# 2015_Receive_LCD.net
KiCad netlist of a schematic drawn in EAGLE
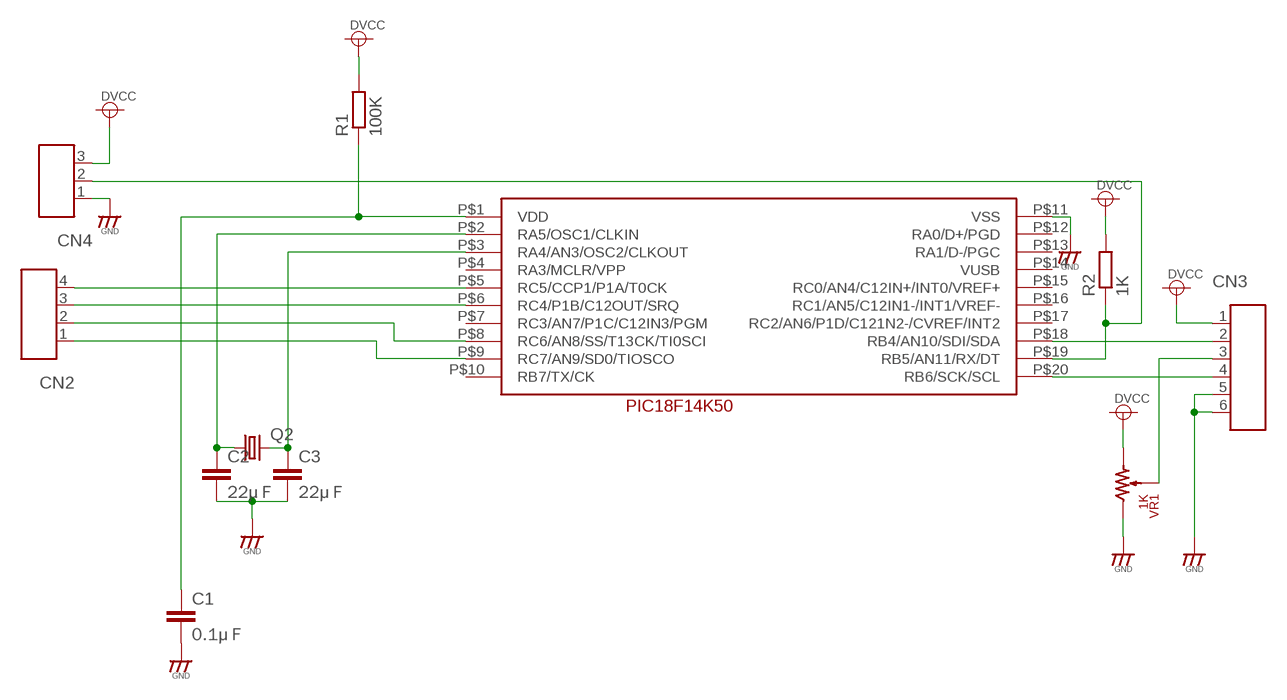
[diagram p0: schematic, sheet 1]

(export (version "E")
  (design (tool "Eeschema 10.0.6"))
  (components
    (comp (ref "C1")
      (value "0.1μＦ")
      (footprint "eagle-import:C025-025X050")
      (libsource (lib "eagle-import") (part "C-EU025-025X050"))
    )
    (comp (ref "C2")
      (value "22μＦ")
      (footprint "eagle-import:C025-025X050")
      (libsource (lib "eagle-import") (part "C-EU025-025X050"))
    )
    (comp (ref "C3")
      (value "22μＦ")
      (footprint "eagle-import:C025-025X050")
      (libsource (lib "eagle-import") (part "C-EU025-025X050"))
    )
    (comp (ref "CN2")
      (value "CON_4P")
      (footprint "eagle-import:CON_HRS_DIP_4")
      (libsource (lib "eagle-import") (part "CON_4P"))
    )
    (comp (ref "CN3")
      (value "CON_6P")
      (footprint "eagle-import:CON_HRS_DIP_6")
      (libsource (lib "eagle-import") (part "CON_6P"))
    )
    (comp (ref "CN4")
      (value "CON_3P")
      (footprint "eagle-import:CON_HRS_DIP_3")
      (libsource (lib "eagle-import") (part "CON_3P"))
    )
    (comp (ref "IC1")
      (value "PIC18F14K50")
      (footprint "eagle-import:PIC18F14K50")
      (libsource (lib "eagle-import") (part "PIC18F14K50"))
    )
    (comp (ref "Q2")
      (value "CRYTALHC49U70")
      (footprint "eagle-import:HC49U70")
      (libsource (lib "eagle-import") (part "CRYTALHC49U70"))
    )
    (comp (ref "R1")
      (value "100K")
      (footprint "eagle-import:0204_7")
      (libsource (lib "eagle-import") (part "R-EU_0204/7"))
    )
    (comp (ref "R2")
      (value "1K")
      (footprint "eagle-import:0204_7")
      (libsource (lib "eagle-import") (part "R-EU_0204/7"))
    )
    (comp (ref "VR1")
      (value "1K")
      (footprint "eagle-import:TRM")
      (libsource (lib "eagle-import") (part "TRM"))
    )
  )
  (nets
    (net (code "1") (name "/RA3{slash}MCLR{slash}VPP") (class "Default")
      (node (ref "IC1") (pin "P$4") (pinfunction "RA3/MCLR/VPP_P$4") (pintype "power_in"))
    )
    (net (code "2") (name "DVCC") (class "Default")
      (node (ref "CN3") (pin "1") (pinfunction "1_1") (pintype "passive"))
      (node (ref "CN4") (pin "3") (pinfunction "3_3") (pintype "passive"))
      (node (ref "R1") (pin "2") (pinfunction "2_2") (pintype "passive"))
      (node (ref "R2") (pin "2") (pinfunction "2_2") (pintype "passive"))
      (node (ref "VR1") (pin "P$1") (pinfunction "P$1_P$1") (pintype "passive"))
    )
    (net (code "3") (name "GND") (class "Default")
      (node (ref "C1") (pin "2") (pinfunction "2_2") (pintype "passive"))
      (node (ref "C2") (pin "2") (pinfunction "2_2") (pintype "passive"))
      (node (ref "C3") (pin "2") (pinfunction "2_2") (pintype "passive"))
      (node (ref "CN3") (pin "5") (pinfunction "5_5") (pintype "passive"))
      (node (ref "CN3") (pin "6") (pinfunction "6_6") (pintype "passive"))
      (node (ref "CN4") (pin "1") (pinfunction "1_1") (pintype "passive"))
      (node (ref "IC1") (pin "P$11") (pinfunction "VSS_P$11") (pintype "power_in"))
      (node (ref "VR1") (pin "P$3") (pinfunction "P$3_P$3") (pintype "passive"))
    )
    (net (code "4") (name "Net-(CN3-Pad3)") (class "Default")
      (node (ref "CN3") (pin "3") (pinfunction "3_3") (pintype "passive"))
      (node (ref "VR1") (pin "P$2") (pinfunction "P$2_P$2") (pintype "passive"))
    )
    (net (code "5") (name "Net-(IC1-RA4{slash}AN3{slash}OSC2{slash}CLKOUT)") (class "Default")
      (node (ref "C3") (pin "1") (pinfunction "1_1") (pintype "passive"))
      (node (ref "IC1") (pin "P$3") (pinfunction "RA4/AN3/OSC2/CLKOUT_P$3") (pintype "bidirectional"))
      (node (ref "Q2") (pin "2") (pinfunction "2_2") (pintype "passive"))
    )
    (net (code "6") (name "Net-(IC1-RA5{slash}OSC1{slash}CLKIN)") (class "Default")
      (node (ref "C2") (pin "1") (pinfunction "1_1") (pintype "passive"))
      (node (ref "IC1") (pin "P$2") (pinfunction "RA5/OSC1/CLKIN_P$2") (pintype "bidirectional"))
      (node (ref "Q2") (pin "1") (pinfunction "1_1") (pintype "passive"))
    )
    (net (code "7") (name "Net-(IC1-RB4{slash}AN10{slash}SDI{slash}SDA)") (class "Default")
      (node (ref "CN3") (pin "2") (pinfunction "2_2") (pintype "passive"))
      (node (ref "IC1") (pin "P$18") (pinfunction "RB4/AN10/SDI/SDA_P$18") (pintype "bidirectional"))
    )
    (net (code "8") (name "Net-(IC1-RB5{slash}AN11{slash}RX{slash}DT)") (class "Default")
      (node (ref "CN4") (pin "2") (pinfunction "2_2") (pintype "passive"))
      (node (ref "IC1") (pin "P$19") (pinfunction "RB5/AN11/RX/DT_P$19") (pintype "bidirectional"))
      (node (ref "R2") (pin "1") (pinfunction "1_1") (pintype "passive"))
    )
    (net (code "9") (name "Net-(IC1-RB6{slash}SCK{slash}SCL)") (class "Default")
      (node (ref "CN3") (pin "4") (pinfunction "4_4") (pintype "passive"))
      (node (ref "IC1") (pin "P$20") (pinfunction "RB6/SCK/SCL_P$20") (pintype "bidirectional"))
    )
    (net (code "10") (name "Net-(IC1-RC4{slash}P1B{slash}C12OUT{slash}SRQ)") (class "Default")
      (node (ref "CN2") (pin "3") (pinfunction "3_3") (pintype "passive"))
      (node (ref "IC1") (pin "P$6") (pinfunction "RC4/P1B/C12OUT/SRQ_P$6") (pintype "bidirectional"))
    )
    (net (code "11") (name "Net-(IC1-RC5{slash}CCP1{slash}P1A{slash}T0CK)") (class "Default")
      (node (ref "CN2") (pin "4") (pinfunction "4_4") (pintype "passive"))
      (node (ref "IC1") (pin "P$5") (pinfunction "RC5/CCP1/P1A/T0CK_P$5") (pintype "bidirectional"))
    )
    (net (code "12") (name "Net-(IC1-RC6{slash}AN8{slash}SS{slash}T13CK{slash}TI0SCI)") (class "Default")
      (node (ref "CN2") (pin "2") (pinfunction "2_2") (pintype "passive"))
      (node (ref "IC1") (pin "P$8") (pinfunction "RC6/AN8/SS/T13CK/TI0SCI_P$8") (pintype "bidirectional"))
    )
    (net (code "13") (name "Net-(IC1-RC7{slash}AN9{slash}SD0{slash}TIOSCO)") (class "Default")
      (node (ref "CN2") (pin "1") (pinfunction "1_1") (pintype "passive"))
      (node (ref "IC1") (pin "P$9") (pinfunction "RC7/AN9/SD0/TIOSCO_P$9") (pintype "bidirectional"))
    )
    (net (code "14") (name "Net-(IC1-VDD)") (class "Default")
      (node (ref "C1") (pin "1") (pinfunction "1_1") (pintype "passive"))
      (node (ref "IC1") (pin "P$1") (pinfunction "VDD_P$1") (pintype "power_in"))
      (node (ref "R1") (pin "1") (pinfunction "1_1") (pintype "passive"))
    )
    (net (code "15") (name "unconnected-(IC1-RA0{slash}D+{slash}PGD-PadP$12)") (class "Default")
      (node (ref "IC1") (pin "P$12") (pinfunction "RA0/D+/PGD_P$12") (pintype "bidirectional"))
    )
    (net (code "16") (name "unconnected-(IC1-RA1{slash}D-{slash}PGC-PadP$13)") (class "Default")
      (node (ref "IC1") (pin "P$13") (pinfunction "RA1/D-/PGC_P$13") (pintype "bidirectional"))
    )
    (net (code "17") (name "unconnected-(IC1-RB7{slash}TX{slash}CK-PadP$10)") (class "Default")
      (node (ref "IC1") (pin "P$10") (pinfunction "RB7/TX/CK_P$10") (pintype "bidirectional"))
    )
    (net (code "18") (name "unconnected-(IC1-RC0{slash}AN4{slash}C12IN+{slash}INT0{slash}VREF+-PadP$15)") (class "Default")
      (node (ref "IC1") (pin "P$15") (pinfunction "RC0/AN4/C12IN+/INT0/VREF+_P$15") (pintype "input"))
    )
    (net (code "19") (name "unconnected-(IC1-RC1{slash}AN5{slash}C12IN1-{slash}INT1{slash}VREF--PadP$16)") (class "Default")
      (node (ref "IC1") (pin "P$16") (pinfunction "RC1/AN5/C12IN1-/INT1/VREF-_P$16") (pintype "bidirectional"))
    )
    (net (code "20") (name "unconnected-(IC1-RC2{slash}AN6{slash}P1D{slash}C121N2-{slash}CVREF{slash}INT2-PadP$17)") (class "Default")
      (node (ref "IC1") (pin "P$17") (pinfunction "RC2/AN6/P1D/C121N2-/CVREF/INT2_P$17") (pintype "bidirectional"))
    )
    (net (code "21") (name "unconnected-(IC1-RC3{slash}AN7{slash}P1C{slash}C12IN3{slash}PGM-PadP$7)") (class "Default")
      (node (ref "IC1") (pin "P$7") (pinfunction "RC3/AN7/P1C/C12IN3/PGM_P$7") (pintype "bidirectional"))
    )
    (net (code "22") (name "unconnected-(IC1-VUSB-PadP$14)") (class "Default")
      (node (ref "IC1") (pin "P$14") (pinfunction "VUSB_P$14") (pintype "bidirectional"))
    )
  )
)
